# Staryu.net
KiCad netlist of a schematic drawn in EAGLE
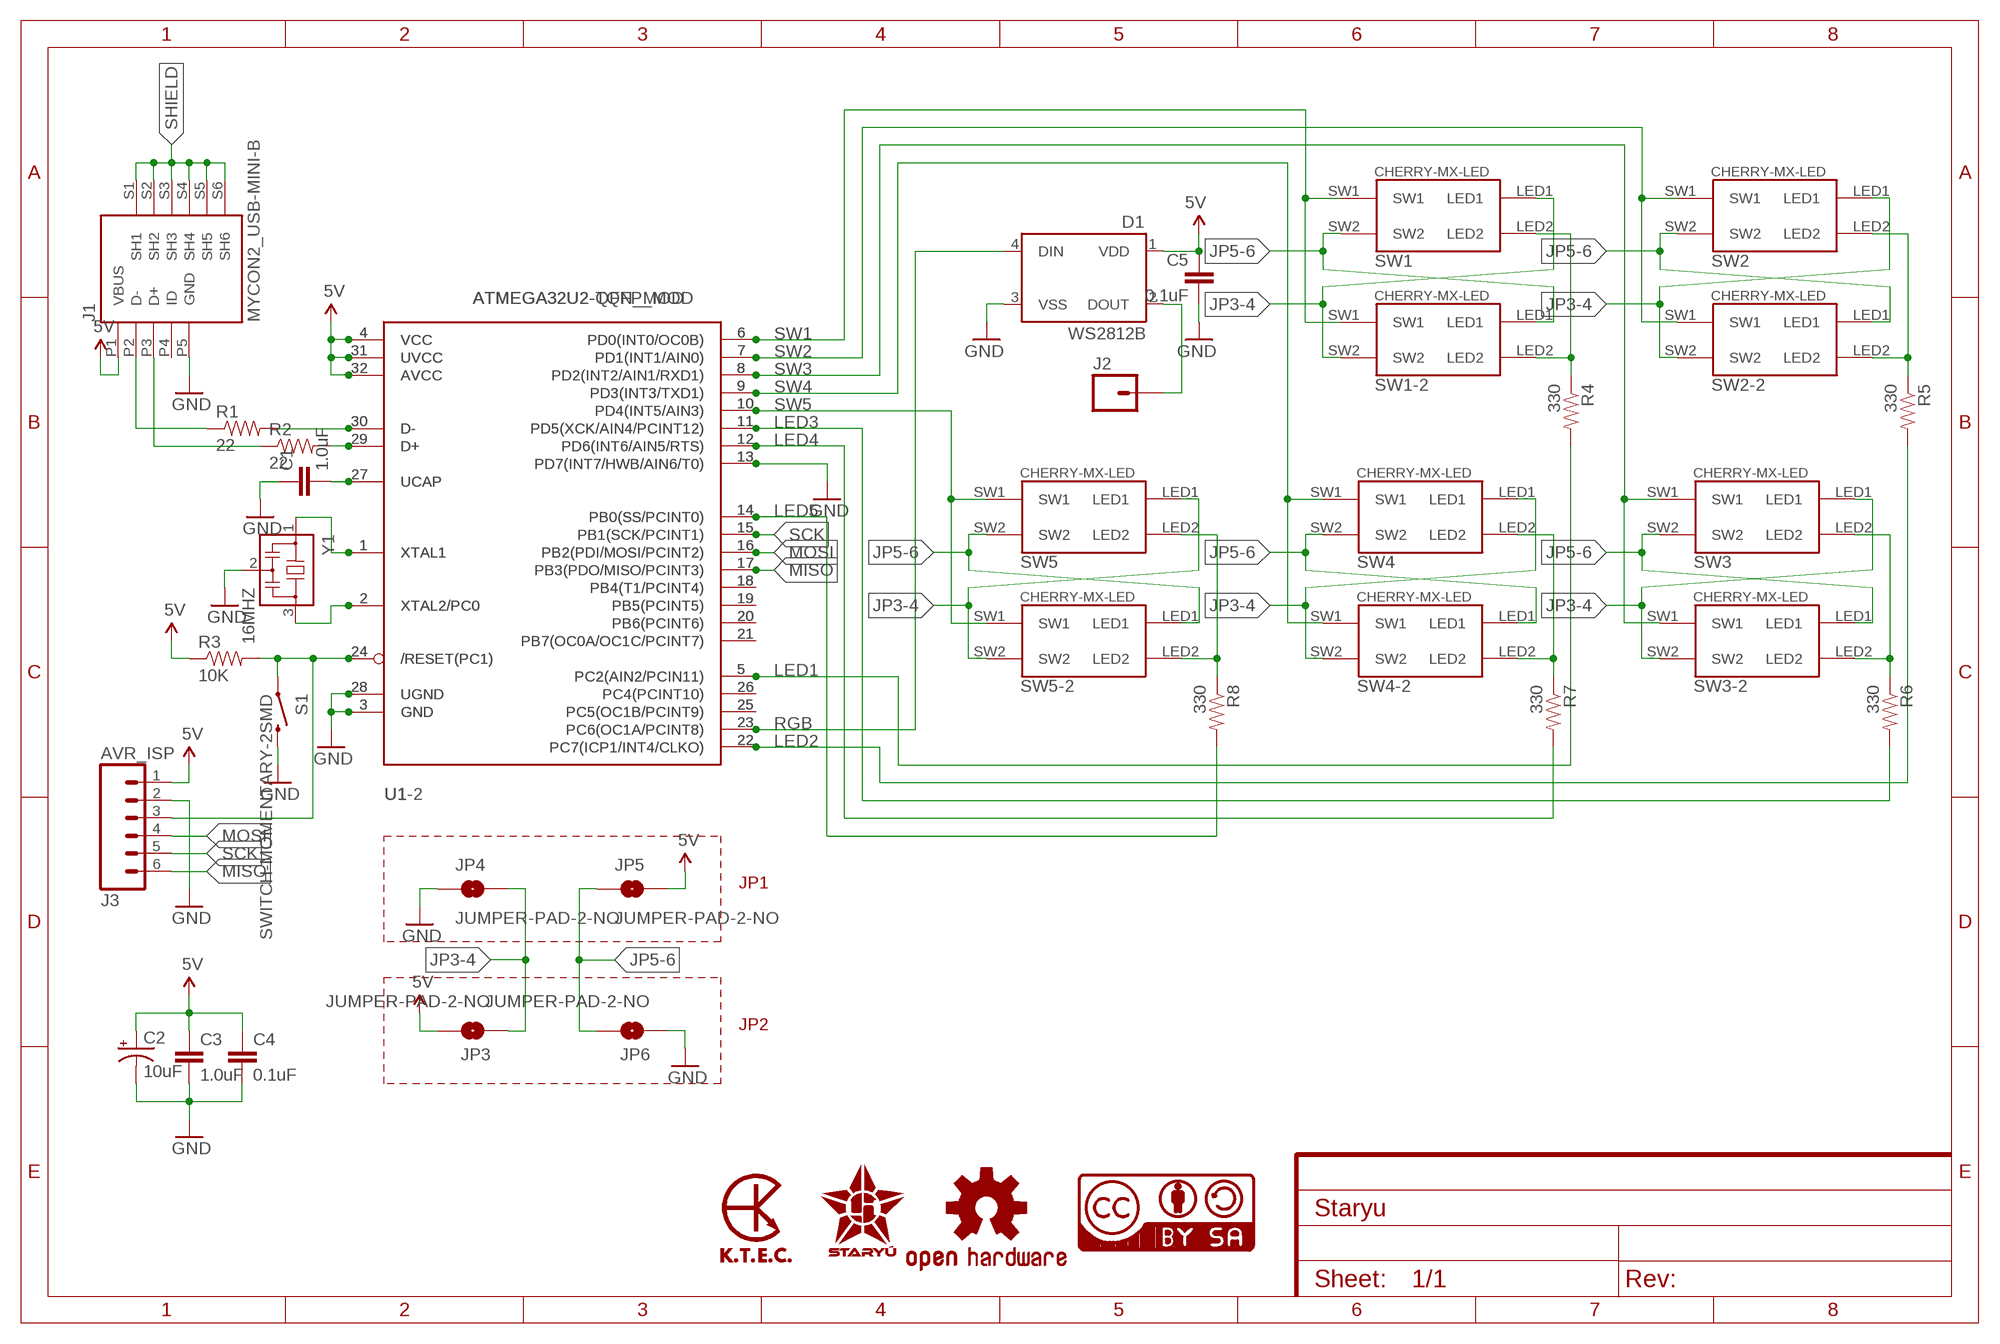
[diagram p0: schematic, sheet 1]

(export (version "E")
  (design (tool "Eeschema 10.0.6"))
  (components
    (comp (ref "C1")
      (value "1.0uF")
      (footprint "eagle-import:0805-CAP")
      (libsource (lib "eagle-import") (part "1.0UF-25V-+80/-20(0805){dblquote}"))
    )
    (comp (ref "C2")
      (value "10uF")
      (footprint "eagle-import:EIA3216")
      (libsource (lib "eagle-import") (part "10UF-16V-10%(TANT)"))
    )
    (comp (ref "C3")
      (value "1.0uF")
      (footprint "eagle-import:0805-CAP")
      (libsource (lib "eagle-import") (part "1.0UF-25V-+80/-20(0805){dblquote}"))
    )
    (comp (ref "C4")
      (value "0.1uF")
      (footprint "eagle-import:0805")
      (libsource (lib "eagle-import") (part "CAP0805"))
    )
    (comp (ref "C5")
      (value "0.1uF")
      (footprint "eagle-import:0805")
      (libsource (lib "eagle-import") (part "CAP0805"))
    )
    (comp (ref "D1")
      (value "WS2812B")
      (footprint "eagle-import:WS2812B_NOSILK")
      (libsource (lib "eagle-import") (part "WS2812BNOSILK"))
    )
    (comp (ref "J1")
      (value "MYCON2_USB-MINI-B")
      (footprint "eagle-import:CON2_USB_MICRO_B_AT")
      (libsource (lib "eagle-import") (part "MYCON2_USB-MINI-B"))
    )
    (comp (ref "J2")
      (value "M01PTH_NO_SILK_YES_STOP")
      (footprint "eagle-import:1X01_NO_SILK")
      (libsource (lib "eagle-import") (part "M01PTH_NO_SILK_YES_STOP"))
    )
    (comp (ref "J3")
      (value "AVR_ISP")
      (footprint "eagle-import:1X06_NO_SILK")
      (libsource (lib "eagle-import") (part "M06NO_SILK_FEMALE_PTH"))
    )
    (comp (ref "JP3")
      (value "JUMPER-PAD-2-NO")
      (footprint "eagle-import:PAD-JUMPER-2-NO_NO_SILK")
      (libsource (lib "eagle-import") (part "JUMPER-PAD-2-NO"))
    )
    (comp (ref "JP4")
      (value "JUMPER-PAD-2-NO")
      (footprint "eagle-import:PAD-JUMPER-2-NO_NO_SILK")
      (libsource (lib "eagle-import") (part "JUMPER-PAD-2-NO"))
    )
    (comp (ref "JP5")
      (value "JUMPER-PAD-2-NO")
      (footprint "eagle-import:PAD-JUMPER-2-NO_NO_SILK")
      (libsource (lib "eagle-import") (part "JUMPER-PAD-2-NO"))
    )
    (comp (ref "JP6")
      (value "JUMPER-PAD-2-NO")
      (footprint "eagle-import:PAD-JUMPER-2-NO_NO_SILK")
      (libsource (lib "eagle-import") (part "JUMPER-PAD-2-NO"))
    )
    (comp (ref "LOGO1")
      (value "K.T.E.C._LOGO3_COPPER_EXP_S")
      (footprint "eagle-import:K.T.E.C._LOGO3_COPPER_EXPOSED_S")
      (libsource (lib "eagle-import") (part "K.T.E.C._LOGO3_COPPER_EXP_S"))
    )
    (comp (ref "LOGO2")
      (value "STARYU_LOGO")
      (footprint "eagle-import:STARYU_LOGO")
      (libsource (lib "eagle-import") (part "STARYU_LOGO"))
    )
    (comp (ref "LOGO3")
      (value "OSHW_LOGOM_EXP")
      (footprint "eagle-import:OSHW_LOGO_COPPER_EXPOSED_M")
      (libsource (lib "eagle-import") (part "OSHW_LOGOM_EXP"))
    )
    (comp (ref "LOGO4")
      (value "CC-BY-SANIX")
      (footprint "eagle-import:CC-BY-SA_NIX")
      (libsource (lib "eagle-import") (part "CC-BY-SANIX"))
    )
    (comp (ref "R1")
      (value "22")
      (footprint "eagle-import:0805")
      (libsource (lib "eagle-import") (part "RESISTOR0805-RES"))
    )
    (comp (ref "R2")
      (value "22")
      (footprint "eagle-import:0805")
      (libsource (lib "eagle-import") (part "RESISTOR0805-RES"))
    )
    (comp (ref "R3")
      (value "10K")
      (footprint "eagle-import:0805")
      (libsource (lib "eagle-import") (part "RESISTOR0805-RES"))
    )
    (comp (ref "R4")
      (value "330")
      (footprint "eagle-import:0805")
      (libsource (lib "eagle-import") (part "RESISTOR0805-RES"))
    )
    (comp (ref "R5")
      (value "330")
      (footprint "eagle-import:0805")
      (libsource (lib "eagle-import") (part "RESISTOR0805-RES"))
    )
    (comp (ref "R6")
      (value "330")
      (footprint "eagle-import:0805")
      (libsource (lib "eagle-import") (part "RESISTOR0805-RES"))
    )
    (comp (ref "R7")
      (value "330")
      (footprint "eagle-import:0805")
      (libsource (lib "eagle-import") (part "RESISTOR0805-RES"))
    )
    (comp (ref "R8")
      (value "330")
      (footprint "eagle-import:0805")
      (libsource (lib "eagle-import") (part "RESISTOR0805-RES"))
    )
    (comp (ref "S1")
      (value "SWITCH-MOMENTARY-2SMD")
      (footprint "eagle-import:TACTILE-SWITCH-SMD")
      (libsource (lib "eagle-import") (part "SWITCH-MOMENTARY-2SMD"))
    )
    (comp (ref "SW1")
      (value "CHERRY-MX-LED-MOD")
      (footprint "eagle-import:CHERRY-MX-LED-MOD")
      (libsource (lib "eagle-import") (part "CHERRY-MX-LED-MOD"))
    )
    (comp (ref "SW1-2")
      (value "CHERRY-MX-LED-MOD")
      (footprint "eagle-import:CHERRY-MX-LED-MOD")
      (libsource (lib "eagle-import") (part "CHERRY-MX-LED-MOD"))
    )
    (comp (ref "SW2")
      (value "CHERRY-MX-LED-MOD")
      (footprint "eagle-import:CHERRY-MX-LED-MOD")
      (libsource (lib "eagle-import") (part "CHERRY-MX-LED-MOD"))
    )
    (comp (ref "SW2-2")
      (value "CHERRY-MX-LED-MOD")
      (footprint "eagle-import:CHERRY-MX-LED-MOD")
      (libsource (lib "eagle-import") (part "CHERRY-MX-LED-MOD"))
    )
    (comp (ref "SW3")
      (value "CHERRY-MX-LED-MOD")
      (footprint "eagle-import:CHERRY-MX-LED-MOD")
      (libsource (lib "eagle-import") (part "CHERRY-MX-LED-MOD"))
    )
    (comp (ref "SW3-2")
      (value "CHERRY-MX-LED-MOD")
      (footprint "eagle-import:CHERRY-MX-LED-MOD")
      (libsource (lib "eagle-import") (part "CHERRY-MX-LED-MOD"))
    )
    (comp (ref "SW4")
      (value "CHERRY-MX-LED-MOD")
      (footprint "eagle-import:CHERRY-MX-LED-MOD")
      (libsource (lib "eagle-import") (part "CHERRY-MX-LED-MOD"))
    )
    (comp (ref "SW4-2")
      (value "CHERRY-MX-LED-MOD")
      (footprint "eagle-import:CHERRY-MX-LED-MOD")
      (libsource (lib "eagle-import") (part "CHERRY-MX-LED-MOD"))
    )
    (comp (ref "SW5")
      (value "CHERRY-MX-LED-MOD")
      (footprint "eagle-import:CHERRY-MX-LED-MOD")
      (libsource (lib "eagle-import") (part "CHERRY-MX-LED-MOD"))
    )
    (comp (ref "SW5-2")
      (value "CHERRY-MX-LED-MOD")
      (footprint "eagle-import:CHERRY-MX-LED-MOD")
      (libsource (lib "eagle-import") (part "CHERRY-MX-LED-MOD"))
    )
    (comp (ref "U1")
      (value "ATMEGA32U2-TQFP_MOD")
      (footprint "eagle-import:TQFP32-08_MOD")
      (libsource (lib "eagle-import") (part "ATMEGA32U2-TQFP_MOD"))
    )
    (comp (ref "U1-2")
      (value "ATMEGA32U2-QFN_MOD")
      (footprint "eagle-import:QFN32_MOD")
      (libsource (lib "eagle-import") (part "ATMEGA32U2-QFN_MOD"))
    )
    (comp (ref "Y1")
      (value "16MHZ")
      (footprint "eagle-import:CST")
      (libsource (lib "eagle-import") (part "CSTCE16M0V53-R0"))
    )
  )
  (nets
    (net (code "1") (name "/LED1") (class "Default")
      (node (ref "R4") (pin "2") (pinfunction "2_2") (pintype "passive"))
      (node (ref "U1") (pin "5") (pinfunction "PC2(AIN2/PCIN11)_5") (pintype "bidirectional"))
      (node (ref "U1-2") (pin "5") (pinfunction "PC2(AIN2/PCIN11)_5") (pintype "bidirectional"))
    )
    (net (code "2") (name "/LED2") (class "Default")
      (node (ref "R5") (pin "2") (pinfunction "2_2") (pintype "passive"))
      (node (ref "U1") (pin "22") (pinfunction "PC7(ICP1/INT4/CLKO)_22") (pintype "bidirectional"))
      (node (ref "U1-2") (pin "22") (pinfunction "PC7(ICP1/INT4/CLKO)_22") (pintype "bidirectional"))
    )
    (net (code "3") (name "/LED3") (class "Default")
      (node (ref "R6") (pin "2") (pinfunction "2_2") (pintype "passive"))
      (node (ref "U1") (pin "11") (pinfunction "PD5(XCK/AIN4/PCINT12)_11") (pintype "bidirectional"))
      (node (ref "U1-2") (pin "11") (pinfunction "PD5(XCK/AIN4/PCINT12)_11") (pintype "bidirectional"))
    )
    (net (code "4") (name "/LED4") (class "Default")
      (node (ref "R7") (pin "2") (pinfunction "2_2") (pintype "passive"))
      (node (ref "U1") (pin "12") (pinfunction "PD6(INT6/AIN5/RTS)_12") (pintype "bidirectional"))
      (node (ref "U1-2") (pin "12") (pinfunction "PD6(INT6/AIN5/RTS)_12") (pintype "bidirectional"))
    )
    (net (code "5") (name "/LED5") (class "Default")
      (node (ref "R8") (pin "2") (pinfunction "2_2") (pintype "passive"))
      (node (ref "U1") (pin "14") (pinfunction "PB0(SS/PCINT0)_14") (pintype "bidirectional"))
      (node (ref "U1-2") (pin "14") (pinfunction "PB0(SS/PCINT0)_14") (pintype "bidirectional"))
    )
    (net (code "6") (name "/RGB") (class "Default")
      (node (ref "D1") (pin "4") (pinfunction "DIN_4") (pintype "input"))
      (node (ref "U1") (pin "23") (pinfunction "PC6(OC1A/PCINT8)_23") (pintype "bidirectional"))
      (node (ref "U1-2") (pin "23") (pinfunction "PC6(OC1A/PCINT8)_23") (pintype "bidirectional"))
    )
    (net (code "7") (name "/SW1") (class "Default")
      (node (ref "SW1") (pin "SW1") (pinfunction "SW1_SW1") (pintype "bidirectional"))
      (node (ref "SW1-2") (pin "SW1") (pinfunction "SW1_SW1") (pintype "bidirectional"))
      (node (ref "U1") (pin "6") (pinfunction "PD0(INT0/OC0B)_6") (pintype "bidirectional"))
      (node (ref "U1-2") (pin "6") (pinfunction "PD0(INT0/OC0B)_6") (pintype "bidirectional"))
    )
    (net (code "8") (name "/SW2") (class "Default")
      (node (ref "SW2") (pin "SW1") (pinfunction "SW1_SW1") (pintype "bidirectional"))
      (node (ref "SW2-2") (pin "SW1") (pinfunction "SW1_SW1") (pintype "bidirectional"))
      (node (ref "U1") (pin "7") (pinfunction "PD1(INT1/AIN0)_7") (pintype "bidirectional"))
      (node (ref "U1-2") (pin "7") (pinfunction "PD1(INT1/AIN0)_7") (pintype "bidirectional"))
    )
    (net (code "9") (name "/SW3") (class "Default")
      (node (ref "SW3") (pin "SW1") (pinfunction "SW1_SW1") (pintype "bidirectional"))
      (node (ref "SW3-2") (pin "SW1") (pinfunction "SW1_SW1") (pintype "bidirectional"))
      (node (ref "U1") (pin "8") (pinfunction "PD2(INT2/AIN1/RXD1)_8") (pintype "bidirectional"))
      (node (ref "U1-2") (pin "8") (pinfunction "PD2(INT2/AIN1/RXD1)_8") (pintype "bidirectional"))
    )
    (net (code "10") (name "/SW4") (class "Default")
      (node (ref "SW4") (pin "SW1") (pinfunction "SW1_SW1") (pintype "bidirectional"))
      (node (ref "SW4-2") (pin "SW1") (pinfunction "SW1_SW1") (pintype "bidirectional"))
      (node (ref "U1") (pin "9") (pinfunction "PD3(INT3/TXD1)_9") (pintype "bidirectional"))
      (node (ref "U1-2") (pin "9") (pinfunction "PD3(INT3/TXD1)_9") (pintype "bidirectional"))
    )
    (net (code "11") (name "/SW5") (class "Default")
      (node (ref "SW5") (pin "SW1") (pinfunction "SW1_SW1") (pintype "bidirectional"))
      (node (ref "SW5-2") (pin "SW1") (pinfunction "SW1_SW1") (pintype "bidirectional"))
      (node (ref "U1") (pin "10") (pinfunction "PD4(INT5/AIN3)_10") (pintype "bidirectional"))
      (node (ref "U1-2") (pin "10") (pinfunction "PD4(INT5/AIN3)_10") (pintype "bidirectional"))
    )
    (net (code "12") (name "5V") (class "Default")
      (node (ref "C2") (pin "A") (pinfunction "+_A") (pintype "passive"))
      (node (ref "C3") (pin "1") (pinfunction "1_1") (pintype "passive"))
      (node (ref "C4") (pin "1") (pinfunction "1_1") (pintype "passive"))
      (node (ref "C5") (pin "1") (pinfunction "1_1") (pintype "passive"))
      (node (ref "D1") (pin "1") (pinfunction "VDD_1") (pintype "power_in"))
      (node (ref "J1") (pin "P1") (pinfunction "VBUS_P1") (pintype "power_in"))
      (node (ref "J3") (pin "1") (pinfunction "1_1") (pintype "passive"))
      (node (ref "JP3") (pin "2") (pinfunction "2_2") (pintype "passive"))
      (node (ref "JP5") (pin "2") (pinfunction "2_2") (pintype "passive"))
      (node (ref "R3") (pin "1") (pinfunction "1_1") (pintype "passive"))
      (node (ref "U1") (pin "31") (pinfunction "UVCC_31") (pintype "bidirectional"))
      (node (ref "U1") (pin "32") (pinfunction "AVCC_32") (pintype "bidirectional"))
      (node (ref "U1") (pin "4") (pinfunction "VCC_4") (pintype "bidirectional"))
      (node (ref "U1-2") (pin "31") (pinfunction "UVCC_31") (pintype "bidirectional"))
      (node (ref "U1-2") (pin "32") (pinfunction "AVCC_32") (pintype "bidirectional"))
      (node (ref "U1-2") (pin "4") (pinfunction "VCC_4") (pintype "bidirectional"))
    )
    (net (code "13") (name "GND") (class "Default")
      (node (ref "C1") (pin "1") (pinfunction "1_1") (pintype "passive"))
      (node (ref "C2") (pin "C") (pinfunction "-_C") (pintype "passive"))
      (node (ref "C3") (pin "2") (pinfunction "2_2") (pintype "passive"))
      (node (ref "C4") (pin "2") (pinfunction "2_2") (pintype "passive"))
      (node (ref "C5") (pin "2") (pinfunction "2_2") (pintype "passive"))
      (node (ref "D1") (pin "3") (pinfunction "VSS_3") (pintype "power_in"))
      (node (ref "J1") (pin "P5") (pinfunction "GND_P5") (pintype "passive"))
      (node (ref "J3") (pin "2") (pinfunction "2_2") (pintype "passive"))
      (node (ref "JP4") (pin "1") (pinfunction "1_1") (pintype "passive"))
      (node (ref "JP6") (pin "1") (pinfunction "1_1") (pintype "passive"))
      (node (ref "S1") (pin "3") (pinfunction "2_3") (pintype "passive"))
      (node (ref "U1") (pin "13") (pinfunction "PD7(INT7/HWB/AIN6/T0)_13") (pintype "bidirectional"))
      (node (ref "U1") (pin "28") (pinfunction "UGND_28") (pintype "bidirectional"))
      (node (ref "U1") (pin "3") (pinfunction "GND_3") (pintype "bidirectional"))
      (node (ref "U1-2") (pin "13") (pinfunction "PD7(INT7/HWB/AIN6/T0)_13") (pintype "bidirectional"))
      (node (ref "U1-2") (pin "28") (pinfunction "UGND_28") (pintype "bidirectional"))
      (node (ref "U1-2") (pin "3") (pinfunction "GND_3") (pintype "bidirectional"))
      (node (ref "Y1") (pin "2") (pinfunction "2_2") (pintype "passive"))
    )
    (net (code "14") (name "JP3-4") (class "Default")
      (node (ref "JP3") (pin "1") (pinfunction "1_1") (pintype "passive"))
      (node (ref "JP4") (pin "2") (pinfunction "2_2") (pintype "passive"))
      (node (ref "SW1") (pin "LED1") (pinfunction "LED1_LED1") (pintype "bidirectional"))
      (node (ref "SW1-2") (pin "SW2") (pinfunction "SW2_SW2") (pintype "bidirectional"))
      (node (ref "SW2") (pin "LED1") (pinfunction "LED1_LED1") (pintype "bidirectional"))
      (node (ref "SW2-2") (pin "SW2") (pinfunction "SW2_SW2") (pintype "bidirectional"))
      (node (ref "SW3") (pin "LED1") (pinfunction "LED1_LED1") (pintype "bidirectional"))
      (node (ref "SW3-2") (pin "SW2") (pinfunction "SW2_SW2") (pintype "bidirectional"))
      (node (ref "SW4") (pin "LED1") (pinfunction "LED1_LED1") (pintype "bidirectional"))
      (node (ref "SW4-2") (pin "SW2") (pinfunction "SW2_SW2") (pintype "bidirectional"))
      (node (ref "SW5") (pin "LED1") (pinfunction "LED1_LED1") (pintype "bidirectional"))
      (node (ref "SW5-2") (pin "SW2") (pinfunction "SW2_SW2") (pintype "bidirectional"))
    )
    (net (code "15") (name "JP5-6") (class "Default")
      (node (ref "JP5") (pin "1") (pinfunction "1_1") (pintype "passive"))
      (node (ref "JP6") (pin "2") (pinfunction "2_2") (pintype "passive"))
      (node (ref "SW1") (pin "SW2") (pinfunction "SW2_SW2") (pintype "bidirectional"))
      (node (ref "SW1-2") (pin "LED1") (pinfunction "LED1_LED1") (pintype "bidirectional"))
      (node (ref "SW2") (pin "SW2") (pinfunction "SW2_SW2") (pintype "bidirectional"))
      (node (ref "SW2-2") (pin "LED1") (pinfunction "LED1_LED1") (pintype "bidirectional"))
      (node (ref "SW3") (pin "SW2") (pinfunction "SW2_SW2") (pintype "bidirectional"))
      (node (ref "SW3-2") (pin "LED1") (pinfunction "LED1_LED1") (pintype "bidirectional"))
      (node (ref "SW4") (pin "SW2") (pinfunction "SW2_SW2") (pintype "bidirectional"))
      (node (ref "SW4-2") (pin "LED1") (pinfunction "LED1_LED1") (pintype "bidirectional"))
      (node (ref "SW5") (pin "SW2") (pinfunction "SW2_SW2") (pintype "bidirectional"))
      (node (ref "SW5-2") (pin "LED1") (pinfunction "LED1_LED1") (pintype "bidirectional"))
    )
    (net (code "16") (name "MISO") (class "Default")
      (node (ref "J3") (pin "6") (pinfunction "6_6") (pintype "passive"))
      (node (ref "U1") (pin "17") (pinfunction "PB3(PDO/MISO/PCINT3)_17") (pintype "bidirectional"))
      (node (ref "U1-2") (pin "17") (pinfunction "PB3(PDO/MISO/PCINT3)_17") (pintype "bidirectional"))
    )
    (net (code "17") (name "MOSI") (class "Default")
      (node (ref "J3") (pin "4") (pinfunction "4_4") (pintype "passive"))
      (node (ref "U1") (pin "16") (pinfunction "PB2(PDI/MOSI/PCINT2)_16") (pintype "bidirectional"))
      (node (ref "U1-2") (pin "16") (pinfunction "PB2(PDI/MOSI/PCINT2)_16") (pintype "bidirectional"))
    )
    (net (code "18") (name "Net-(D1-DOUT)") (class "Default")
      (node (ref "D1") (pin "2") (pinfunction "DOUT_2") (pintype "output"))
      (node (ref "J2") (pin "1") (pinfunction "1_1") (pintype "passive"))
    )
    (net (code "19") (name "Net-(J1-D+)") (class "Default")
      (node (ref "J1") (pin "P3") (pinfunction "D+_P3") (pintype "bidirectional"))
      (node (ref "R2") (pin "1") (pinfunction "1_1") (pintype "passive"))
    )
    (net (code "20") (name "Net-(J1-D-)") (class "Default")
      (node (ref "J1") (pin "P2") (pinfunction "D-_P2") (pintype "bidirectional"))
      (node (ref "R1") (pin "1") (pinfunction "1_1") (pintype "passive"))
    )
    (net (code "21") (name "Net-(R4-Pad1)") (class "Default")
      (node (ref "R4") (pin "1") (pinfunction "1_1") (pintype "passive"))
      (node (ref "SW1") (pin "LED2") (pinfunction "LED2_LED2") (pintype "bidirectional"))
      (node (ref "SW1-2") (pin "LED2") (pinfunction "LED2_LED2") (pintype "bidirectional"))
    )
    (net (code "22") (name "Net-(R5-Pad1)") (class "Default")
      (node (ref "R5") (pin "1") (pinfunction "1_1") (pintype "passive"))
      (node (ref "SW2") (pin "LED2") (pinfunction "LED2_LED2") (pintype "bidirectional"))
      (node (ref "SW2-2") (pin "LED2") (pinfunction "LED2_LED2") (pintype "bidirectional"))
    )
    (net (code "23") (name "Net-(R6-Pad1)") (class "Default")
      (node (ref "R6") (pin "1") (pinfunction "1_1") (pintype "passive"))
      (node (ref "SW3") (pin "LED2") (pinfunction "LED2_LED2") (pintype "bidirectional"))
      (node (ref "SW3-2") (pin "LED2") (pinfunction "LED2_LED2") (pintype "bidirectional"))
    )
    (net (code "24") (name "Net-(R7-Pad1)") (class "Default")
      (node (ref "R7") (pin "1") (pinfunction "1_1") (pintype "passive"))
      (node (ref "SW4") (pin "LED2") (pinfunction "LED2_LED2") (pintype "bidirectional"))
      (node (ref "SW4-2") (pin "LED2") (pinfunction "LED2_LED2") (pintype "bidirectional"))
    )
    (net (code "25") (name "Net-(R8-Pad1)") (class "Default")
      (node (ref "R8") (pin "1") (pinfunction "1_1") (pintype "passive"))
      (node (ref "SW5") (pin "LED2") (pinfunction "LED2_LED2") (pintype "bidirectional"))
      (node (ref "SW5-2") (pin "LED2") (pinfunction "LED2_LED2") (pintype "bidirectional"))
    )
    (net (code "26") (name "Net-(U1-2-D+)") (class "Default")
      (node (ref "R2") (pin "2") (pinfunction "2_2") (pintype "passive"))
      (node (ref "U1") (pin "29") (pinfunction "D+_29") (pintype "bidirectional"))
      (node (ref "U1-2") (pin "29") (pinfunction "D+_29") (pintype "bidirectional"))
    )
    (net (code "27") (name "Net-(U1-2-D-)") (class "Default")
      (node (ref "R1") (pin "2") (pinfunction "2_2") (pintype "passive"))
      (node (ref "U1") (pin "30") (pinfunction "D-_30") (pintype "bidirectional"))
      (node (ref "U1-2") (pin "30") (pinfunction "D-_30") (pintype "bidirectional"))
    )
    (net (code "28") (name "Net-(U1-2-PB4(T1{slash}PCINT4))") (class "Default")
      (node (ref "U1") (pin "18") (pinfunction "PB4(T1/PCINT4)_18") (pintype "bidirectional"))
      (node (ref "U1-2") (pin "18") (pinfunction "PB4(T1/PCINT4)_18") (pintype "bidirectional"))
    )
    (net (code "29") (name "Net-(U1-2-PB5(PCINT5))") (class "Default")
      (node (ref "U1") (pin "19") (pinfunction "PB5(PCINT5)_19") (pintype "bidirectional"))
      (node (ref "U1-2") (pin "19") (pinfunction "PB5(PCINT5)_19") (pintype "bidirectional"))
    )
    (net (code "30") (name "Net-(U1-2-PB6(PCINT6))") (class "Default")
      (node (ref "U1") (pin "20") (pinfunction "PB6(PCINT6)_20") (pintype "bidirectional"))
      (node (ref "U1-2") (pin "20") (pinfunction "PB6(PCINT6)_20") (pintype "bidirectional"))
    )
    (net (code "31") (name "Net-(U1-2-PB7(OC0A{slash}OC1C{slash}PCINT7))") (class "Default")
      (node (ref "U1") (pin "21") (pinfunction "PB7(OC0A/OC1C/PCINT7)_21") (pintype "bidirectional"))
      (node (ref "U1-2") (pin "21") (pinfunction "PB7(OC0A/OC1C/PCINT7)_21") (pintype "bidirectional"))
    )
    (net (code "32") (name "Net-(U1-2-PC4(PCINT10))") (class "Default")
      (node (ref "U1") (pin "26") (pinfunction "PC4(PCINT10)_26") (pintype "bidirectional"))
      (node (ref "U1-2") (pin "26") (pinfunction "PC4(PCINT10)_26") (pintype "bidirectional"))
    )
    (net (code "33") (name "Net-(U1-2-PC5(OC1B{slash}PCINT9))") (class "Default")
      (node (ref "U1") (pin "25") (pinfunction "PC5(OC1B/PCINT9)_25") (pintype "bidirectional"))
      (node (ref "U1-2") (pin "25") (pinfunction "PC5(OC1B/PCINT9)_25") (pintype "bidirectional"))
    )
    (net (code "34") (name "Net-(U1-2-UCAP)") (class "Default")
      (node (ref "C1") (pin "2") (pinfunction "2_2") (pintype "passive"))
      (node (ref "U1") (pin "27") (pinfunction "UCAP_27") (pintype "bidirectional"))
      (node (ref "U1-2") (pin "27") (pinfunction "UCAP_27") (pintype "bidirectional"))
    )
    (net (code "35") (name "Net-(U1-2-XTAL1)") (class "Default")
      (node (ref "U1") (pin "1") (pinfunction "XTAL1_1") (pintype "bidirectional"))
      (node (ref "U1-2") (pin "1") (pinfunction "XTAL1_1") (pintype "bidirectional"))
      (node (ref "Y1") (pin "1") (pinfunction "1_1") (pintype "passive"))
    )
    (net (code "36") (name "Net-(U1-2-XTAL2{slash}PC0)") (class "Default")
      (node (ref "U1") (pin "2") (pinfunction "XTAL2/PC0_2") (pintype "bidirectional"))
      (node (ref "U1-2") (pin "2") (pinfunction "XTAL2/PC0_2") (pintype "bidirectional"))
      (node (ref "Y1") (pin "3") (pinfunction "3_3") (pintype "passive"))
    )
    (net (code "37") (name "Net-(U1-2-{slash}RESET(PC1))") (class "Default")
      (node (ref "J3") (pin "3") (pinfunction "3_3") (pintype "passive"))
      (node (ref "R3") (pin "2") (pinfunction "2_2") (pintype "passive"))
      (node (ref "S1") (pin "1") (pinfunction "1_1") (pintype "passive"))
      (node (ref "U1") (pin "24") (pinfunction "/RESET(PC1)_24") (pintype "bidirectional"))
      (node (ref "U1-2") (pin "24") (pinfunction "/RESET(PC1)_24") (pintype "bidirectional"))
    )
    (net (code "38") (name "SCK") (class "Default")
      (node (ref "J3") (pin "5") (pinfunction "5_5") (pintype "passive"))
      (node (ref "U1") (pin "15") (pinfunction "PB1(SCK/PCINT1)_15") (pintype "bidirectional"))
      (node (ref "U1-2") (pin "15") (pinfunction "PB1(SCK/PCINT1)_15") (pintype "bidirectional"))
    )
    (net (code "39") (name "SHIELD") (class "Default")
      (node (ref "J1") (pin "S1") (pinfunction "SH1_S1") (pintype "passive"))
      (node (ref "J1") (pin "S2") (pinfunction "SH2_S2") (pintype "passive"))
      (node (ref "J1") (pin "S3") (pinfunction "SH3_S3") (pintype "passive"))
      (node (ref "J1") (pin "S4") (pinfunction "SH4_S4") (pintype "passive"))
      (node (ref "J1") (pin "S5") (pinfunction "SH5_S5") (pintype "passive"))
      (node (ref "J1") (pin "S6") (pinfunction "SH6_S6") (pintype "passive"))
    )
    (net (code "40") (name "unconnected-(J1-ID-PadP4)") (class "Default")
      (node (ref "J1") (pin "P4") (pinfunction "ID_P4") (pintype "bidirectional"))
    )
  )
)
